# 2_AD9833.net
KiCad netlist of a schematic drawn in Altium Designer
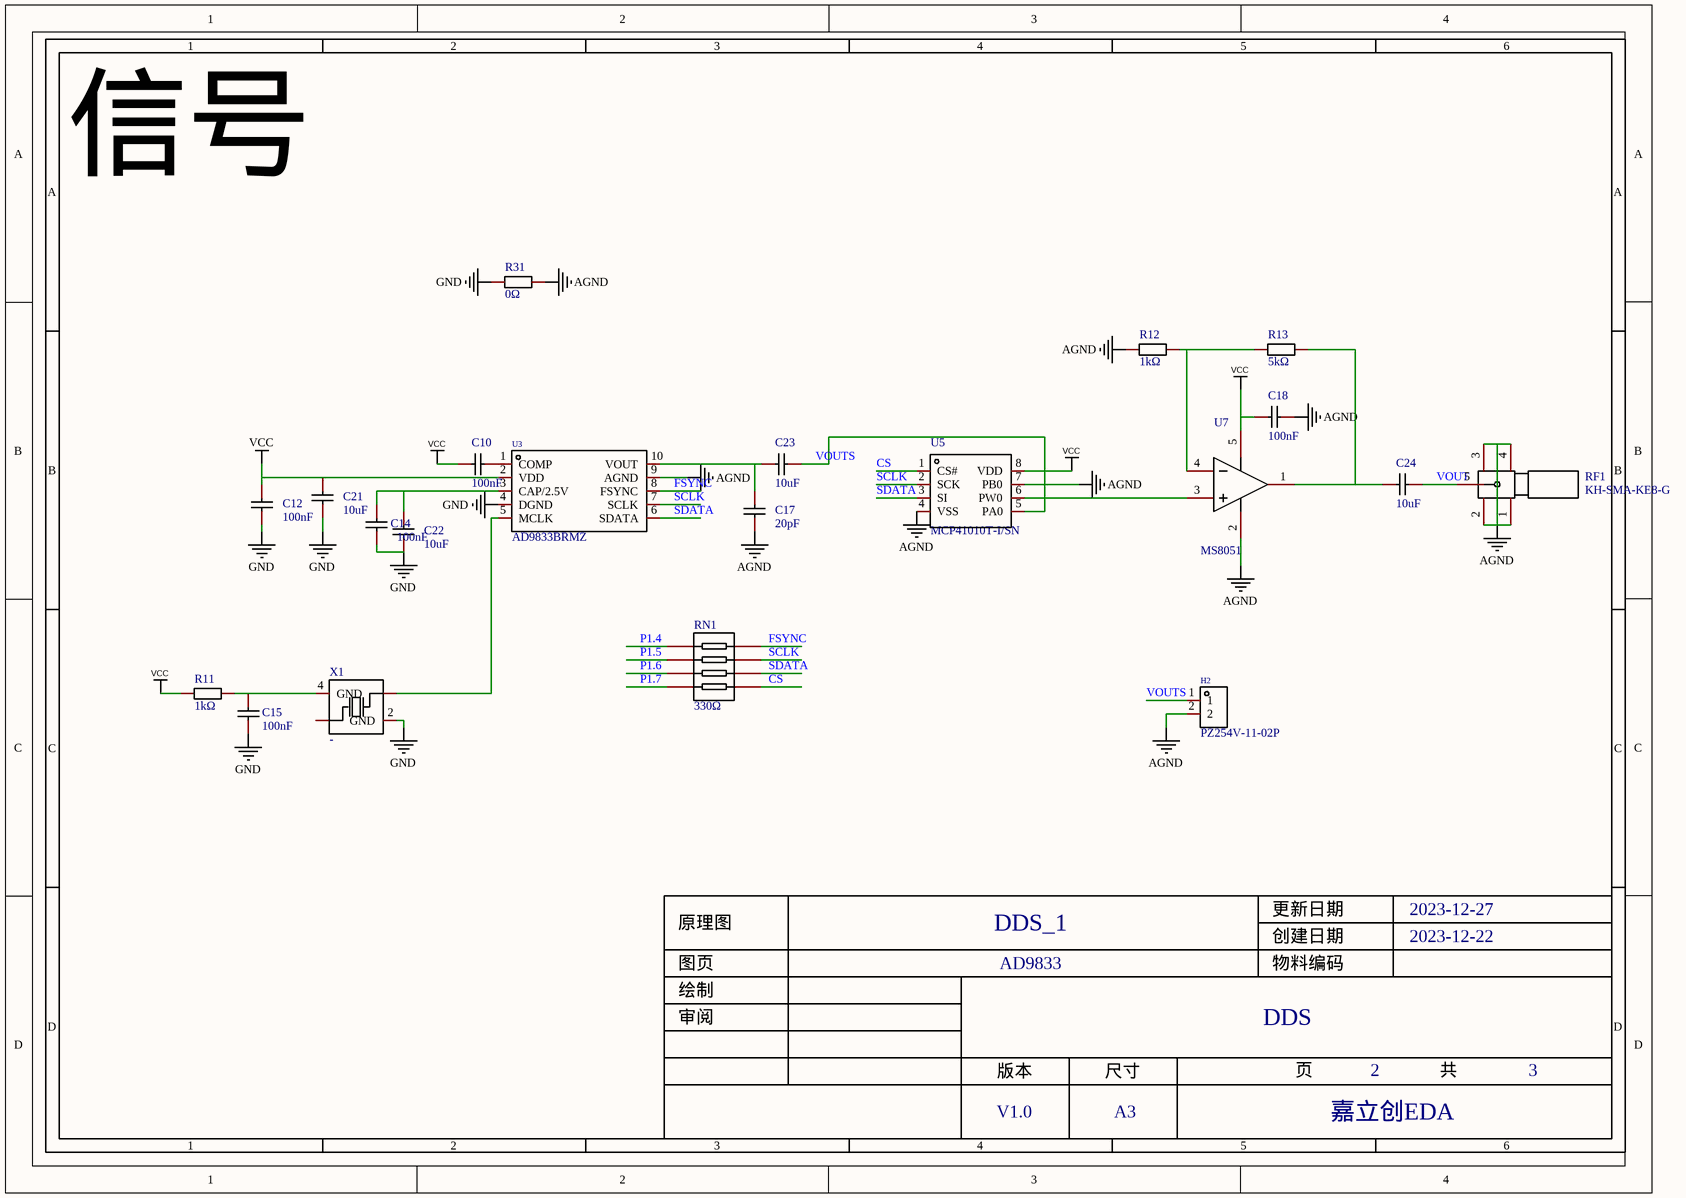
[diagram p0: 2_AD9833.schdoc]

(export (version "E")
  (design (tool "Eeschema 10.0.6"))
  (components
    (comp (ref "C10")
      (value "100nF")
      (description "容值:100nF;精度:±10%;额定电压:50V;材质(温度系数):X7R;")
      (fields
        (field (name "NAME") "100nF")
        (field (name "MANUFACTURER") "FH(风华)")
        (field (name "MANUFACTURER PART") "0805B104K500NT")
      )
      (libsource (lib "altium-import") (part "root_0_0805B104K500NT_"))
    )
    (comp (ref "C12")
      (value "100nF")
      (description "容值:100nF;精度:±10%;额定电压:50V;材质(温度系数):X7R;")
      (fields
        (field (name "NAME") "100nF")
        (field (name "MANUFACTURER") "FH(风华)")
        (field (name "MANUFACTURER PART") "0805B104K500NT")
      )
      (libsource (lib "altium-import") (part "root_1_0805B104K500NT_"))
    )
    (comp (ref "C14")
      (value "100nF")
      (description "容值:100nF;精度:±10%;额定电压:50V;材质(温度系数):X7R;")
      (fields
        (field (name "NAME") "100nF")
        (field (name "MANUFACTURER") "FH(风华)")
        (field (name "MANUFACTURER PART") "0805B104K500NT")
      )
      (libsource (lib "altium-import") (part "root_1_0805B104K500NT_"))
    )
    (comp (ref "C15")
      (value "100nF")
      (description "容值:100nF;精度:±10%;额定电压:50V;材质(温度系数):X7R;")
      (fields
        (field (name "NAME") "100nF")
        (field (name "MANUFACTURER") "FH(风华)")
        (field (name "MANUFACTURER PART") "0805B104K500NT")
      )
      (libsource (lib "altium-import") (part "root_1_0805B104K500NT_"))
    )
    (comp (ref "C17")
      (value "20pF")
      (description "容值:100nF;精度:±10%;额定电压:50V;材质(温度系数):X7R;")
      (fields
        (field (name "NAME") "20pF")
        (field (name "MANUFACTURER") "FH(风华)")
        (field (name "MANUFACTURER PART") "0805B104K500NT")
      )
      (libsource (lib "altium-import") (part "root_1_0805B104K500NT_"))
    )
    (comp (ref "C18")
      (value "100nF")
      (description "容值:100nF;精度:±10%;额定电压:50V;材质(温度系数):X7R;")
      (fields
        (field (name "NAME") "100nF")
        (field (name "MANUFACTURER") "FH(风华)")
        (field (name "MANUFACTURER PART") "0805B104K500NT")
      )
      (libsource (lib "altium-import") (part "root_0_0805B104K500NT_"))
    )
    (comp (ref "C21")
      (value "10uF")
      (description "容值:10uF;精度:±10%;额定电压:50V;材质(温度系数):X5R;")
      (fields
        (field (name "NAME") "10uF")
        (field (name "MANUFACTURER") "SAMSUNG(三星)")
        (field (name "MANUFACTURER PART") "CL31A106KBHNNNE")
      )
      (libsource (lib "altium-import") (part "root_1_CL31A106KBHNNNE_"))
    )
    (comp (ref "C22")
      (value "10uF")
      (description "容值:10uF;精度:±10%;额定电压:50V;材质(温度系数):X5R;")
      (fields
        (field (name "NAME") "10uF")
        (field (name "MANUFACTURER") "SAMSUNG(三星)")
        (field (name "MANUFACTURER PART") "CL31A106KBHNNNE")
      )
      (libsource (lib "altium-import") (part "root_1_CL31A106KBHNNNE_"))
    )
    (comp (ref "C23")
      (value "10uF")
      (description "容值:10uF;精度:±10%;额定电压:50V;材质(温度系数):X5R;")
      (fields
        (field (name "NAME") "10uF")
        (field (name "MANUFACTURER") "SAMSUNG(三星)")
        (field (name "MANUFACTURER PART") "CL31A106KBHNNNE")
      )
      (libsource (lib "altium-import") (part "root_0_CL31A106KBHNNNE_"))
    )
    (comp (ref "C24")
      (value "10uF")
      (description "容值:10uF;精度:±10%;额定电压:50V;材质(温度系数):X5R;")
      (fields
        (field (name "NAME") "10uF")
        (field (name "MANUFACTURER") "SAMSUNG(三星)")
        (field (name "MANUFACTURER PART") "CL31A106KBHNNNE")
      )
      (libsource (lib "altium-import") (part "root_0_CL31A106KBHNNNE_"))
    )
    (comp (ref "H2")
      (value "PZ254V-11-02P")
      (fields (field (name "NAME") "PZ254V-11-02P") (field (name "MANUFACTURER") "XFCN(兴飞)"))
      (libsource (lib "altium-import") (part "root_0_PZ254V-11-02P_"))
    )
    (comp (ref "R11")
      (value "1kΩ")
      (description "阻值:1kΩ;精度:±1%;功率:125mW;温度系数:±100ppm/℃;电阻类型:厚膜电阻;")
      (fields
        (field (name "NAME") "1kΩ")
        (field (name "MANUFACTURER") "UNI-ROYAL(厚声)")
        (field (name "MANUFACTURER PART") "0805W8F1001T5E")
      )
      (libsource (lib "altium-import") (part "root_0_0805W8F1001T5E_"))
    )
    (comp (ref "R12")
      (value "1kΩ")
      (description "阻值:1kΩ;精度:±1%;功率:125mW;温度系数:±100ppm/℃;电阻类型:厚膜电阻;")
      (fields
        (field (name "NAME") "1kΩ")
        (field (name "MANUFACTURER") "UNI-ROYAL(厚声)")
        (field (name "MANUFACTURER PART") "0805W8F1001T5E")
      )
      (libsource (lib "altium-import") (part "root_0_0805W8F1001T5E_"))
    )
    (comp (ref "R13")
      (value "5kΩ")
      (description "阻值:1kΩ;精度:±1%;功率:125mW;温度系数:±100ppm/℃;电阻类型:厚膜电阻;")
      (fields
        (field (name "NAME") "5kΩ")
        (field (name "MANUFACTURER") "UNI-ROYAL(厚声)")
        (field (name "MANUFACTURER PART") "0805W8F1001T5E")
      )
      (libsource (lib "altium-import") (part "root_0_0805W8F1001T5E_"))
    )
    (comp (ref "R31")
      (value "0Ω")
      (description "电阻类型:厚膜电阻;阻值:0Ω;精度:±1%;功率:125mW;")
      (fields
        (field (name "NAME") "0Ω")
        (field (name "MANUFACTURER") "UNI-ROYAL(厚声)")
        (field (name "MANUFACTURER PART") "0805W8F0000T5E")
      )
      (libsource (lib "altium-import") (part "root_0_0805W8F0000T5E_"))
    )
    (comp (ref "RF1")
      (value "KH-SMA-KE8-G")
      (description "连接器类型:板端;接口类型:内孔;频率-最大值:-;接口直径:-;射频系列:SMA;端口数量:1;阻抗:-;样式:偏脚;接口长度/高度:8mm;工作温度范围:-;")
      (fields (field (name "NAME") "KH-SMA-KE8-G") (field (name "MANUFACTURER") "kinghelm(金航标)"))
      (libsource (lib "altium-import") (part "root_2_KH-SMA-KE8-G_"))
    )
    (comp (ref "RN1")
      (value "330Ω")
      (description "阻值:330Ω;精度:±5%;单个元件功率:62.5mW;电阻器数:4;温度系数:±200ppm/℃;")
      (fields
        (field (name "NAME") "330Ω")
        (field (name "MANUFACTURER") "UNI-ROYAL(厚声)")
        (field (name "MANUFACTURER PART") "4D03WGJ0331T5E")
      )
      (libsource (lib "altium-import") (part "root_0_4D03WGJ0331T5E_"))
    )
    (comp (ref "U3")
      (value "AD9833BRMZ")
      (description "电源电压:2.3V~5.5V;分辨率(位):10;自宽调谐(最大值):28b;")
      (fields (field (name "NAME") "AD9833BRMZ") (field (name "MANUFACTURER") "ADI(亚德诺)"))
      (libsource (lib "altium-import") (part "root_0_AD9833BRMZ_"))
    )
    (comp (ref "U5")
      (value "MCP41010T-I/SN")
      (description "供电电压:2.7V~5.5V;电阻值(欧姆):10kΩ;精度:±20%;接口类型:SPI;")
      (fields (field (name "NAME") "MCP41010T-I/SN") (field (name "MANUFACTURER") "MICROCHIP(美国微芯)"))
      (libsource (lib "altium-import") (part "root_0_MCP41010T-I/SN_"))
    )
    (comp (ref "U7")
      (value "MS8051")
      (description "运放类型:-;放大器组数:-;增益带宽积（GBP）:-;压摆率（SR）:-;电源电压:-;各通道供电电流:-;")
      (fields (field (name "NAME") "MS8051") (field (name "MANUFACTURER") "Corebai(芯佰微)"))
      (libsource (lib "altium-import") (part "root_0_CBM8051AST5_"))
    )
    (comp (ref "X1")
      (value "-")
      (description "频率:-;负载电容:-;")
      (fields
        (field (name "NAME") "-")
        (field (name "MANUFACTURER") "TKD(泰晶)")
        (field (name "MANUFACTURER PART") "SX32Y025000BK1T")
      )
      (libsource (lib "altium-import") (part "root_0_SX32Y025000BK1T_"))
    )
  )
  (nets
    (net (code "1") (name "/CS") (class "Default")
      (node (ref "RN1") (pin "5") (pinfunction "5_5") (pintype "passive"))
      (node (ref "U5") (pin "1") (pinfunction "CS#_1") (pintype "passive"))
    )
    (net (code "2") (name "/FSYNC") (class "Default")
      (node (ref "RN1") (pin "8") (pinfunction "8_8") (pintype "passive"))
      (node (ref "U3") (pin "8") (pinfunction "FSYNC_8") (pintype "passive"))
    )
    (net (code "3") (name "/P1.4") (class "Default")
      (node (ref "RN1") (pin "1") (pinfunction "1_1") (pintype "passive"))
    )
    (net (code "4") (name "/P1.5") (class "Default")
      (node (ref "RN1") (pin "2") (pinfunction "2_2") (pintype "passive"))
    )
    (net (code "5") (name "/P1.6") (class "Default")
      (node (ref "RN1") (pin "3") (pinfunction "3_3") (pintype "passive"))
    )
    (net (code "6") (name "/P1.7") (class "Default")
      (node (ref "RN1") (pin "4") (pinfunction "4_4") (pintype "passive"))
    )
    (net (code "7") (name "/SCLK") (class "Default")
      (node (ref "RN1") (pin "7") (pinfunction "7_7") (pintype "passive"))
      (node (ref "U3") (pin "7") (pinfunction "SCLK_7") (pintype "passive"))
      (node (ref "U5") (pin "2") (pinfunction "SCK_2") (pintype "passive"))
    )
    (net (code "8") (name "/SDATA") (class "Default")
      (node (ref "RN1") (pin "6") (pinfunction "6_6") (pintype "passive"))
      (node (ref "U3") (pin "6") (pinfunction "SDATA_6") (pintype "passive"))
      (node (ref "U5") (pin "3") (pinfunction "SI_3") (pintype "passive"))
    )
    (net (code "9") (name "/VOUT") (class "Default")
      (node (ref "C24") (pin "2") (pinfunction "2_2") (pintype "passive"))
      (node (ref "RF1") (pin "5") (pinfunction "5_5") (pintype "passive"))
    )
    (net (code "10") (name "/VOUTS") (class "Default")
      (node (ref "C23") (pin "2") (pinfunction "2_2") (pintype "passive"))
      (node (ref "H2") (pin "1") (pinfunction "1_1") (pintype "passive"))
      (node (ref "U5") (pin "5") (pinfunction "PA0_5") (pintype "passive"))
    )
    (net (code "11") (name "AGND") (class "Default")
      (node (ref "C17") (pin "1") (pinfunction "1_1") (pintype "passive"))
      (node (ref "C18") (pin "2") (pinfunction "2_2") (pintype "passive"))
      (node (ref "H2") (pin "2") (pinfunction "2_2") (pintype "passive"))
      (node (ref "R12") (pin "1") (pinfunction "1_1") (pintype "passive"))
      (node (ref "R31") (pin "2") (pinfunction "2_2") (pintype "passive"))
      (node (ref "RF1") (pin "1") (pinfunction "1_1") (pintype "passive"))
      (node (ref "RF1") (pin "2") (pinfunction "2_2") (pintype "passive"))
      (node (ref "RF1") (pin "3") (pinfunction "3_3") (pintype "passive"))
      (node (ref "RF1") (pin "4") (pinfunction "4_4") (pintype "passive"))
      (node (ref "U3") (pin "9") (pinfunction "AGND_9") (pintype "passive"))
      (node (ref "U5") (pin "4") (pinfunction "VSS_4") (pintype "passive"))
      (node (ref "U5") (pin "7") (pinfunction "PB0_7") (pintype "passive"))
      (node (ref "U7") (pin "2") (pinfunction "VSS_2") (pintype "passive"))
    )
    (net (code "12") (name "GND") (class "Default")
      (node (ref "C12") (pin "1") (pinfunction "1_1") (pintype "passive"))
      (node (ref "C14") (pin "1") (pinfunction "1_1") (pintype "passive"))
      (node (ref "C15") (pin "1") (pinfunction "1_1") (pintype "passive"))
      (node (ref "C21") (pin "1") (pinfunction "1_1") (pintype "passive"))
      (node (ref "C22") (pin "1") (pinfunction "1_1") (pintype "passive"))
      (node (ref "R31") (pin "1") (pinfunction "1_1") (pintype "passive"))
      (node (ref "U3") (pin "4") (pinfunction "DGND_4") (pintype "passive"))
      (node (ref "X1") (pin "2") (pinfunction "GND_2") (pintype "passive"))
    )
    (net (code "13") (name "Net-(C15-Pad2)") (class "Default")
      (node (ref "C15") (pin "2") (pinfunction "2_2") (pintype "passive"))
      (node (ref "R11") (pin "2") (pinfunction "2_2") (pintype "passive"))
      (node (ref "X1") (pin "4") (pinfunction "GND_4") (pintype "passive"))
    )
    (net (code "14") (name "Net-(U3-CAP{slash}2.5V)") (class "Default")
      (node (ref "C14") (pin "2") (pinfunction "2_2") (pintype "passive"))
      (node (ref "C22") (pin "2") (pinfunction "2_2") (pintype "passive"))
      (node (ref "U3") (pin "3") (pinfunction "CAP/2.5V_3") (pintype "passive"))
    )
    (net (code "15") (name "Net-(U3-COMP)") (class "Default")
      (node (ref "C10") (pin "2") (pinfunction "2_2") (pintype "passive"))
      (node (ref "U3") (pin "1") (pinfunction "COMP_1") (pintype "passive"))
    )
    (net (code "16") (name "Net-(U3-MCLK)") (class "Default")
      (node (ref "U3") (pin "5") (pinfunction "MCLK_5") (pintype "passive"))
      (node (ref "X1") (pin "3") (pinfunction "OSC2_3") (pintype "passive"))
    )
    (net (code "17") (name "Net-(U3-VOUT)") (class "Default")
      (node (ref "C17") (pin "2") (pinfunction "2_2") (pintype "passive"))
      (node (ref "C23") (pin "1") (pinfunction "1_1") (pintype "passive"))
      (node (ref "U3") (pin "10") (pinfunction "VOUT_10") (pintype "passive"))
    )
    (net (code "18") (name "Net-(U5-PW0)") (class "Default")
      (node (ref "U5") (pin "6") (pinfunction "PW0_6") (pintype "passive"))
      (node (ref "U7") (pin "3") (pinfunction "IN+_3") (pintype "passive"))
    )
    (net (code "19") (name "Net-(U7-IN-)") (class "Default")
      (node (ref "R12") (pin "2") (pinfunction "2_2") (pintype "passive"))
      (node (ref "R13") (pin "1") (pinfunction "1_1") (pintype "passive"))
      (node (ref "U7") (pin "4") (pinfunction "IN-_4") (pintype "passive"))
    )
    (net (code "20") (name "Net-(U7-OUT)") (class "Default")
      (node (ref "C24") (pin "1") (pinfunction "1_1") (pintype "passive"))
      (node (ref "R13") (pin "2") (pinfunction "2_2") (pintype "passive"))
      (node (ref "U7") (pin "1") (pinfunction "OUT_1") (pintype "passive"))
    )
    (net (code "21") (name "VCC") (class "Default")
      (node (ref "C10") (pin "1") (pinfunction "1_1") (pintype "passive"))
      (node (ref "C12") (pin "2") (pinfunction "2_2") (pintype "passive"))
      (node (ref "C18") (pin "1") (pinfunction "1_1") (pintype "passive"))
      (node (ref "C21") (pin "2") (pinfunction "2_2") (pintype "passive"))
      (node (ref "R11") (pin "1") (pinfunction "1_1") (pintype "passive"))
      (node (ref "U3") (pin "2") (pinfunction "VDD_2") (pintype "passive"))
      (node (ref "U5") (pin "8") (pinfunction "VDD_8") (pintype "passive"))
      (node (ref "U7") (pin "5") (pinfunction "VDD_5") (pintype "passive"))
    )
    (net (code "22") (name "unconnected-(X1-OSC1-Pad1)") (class "Default")
      (node (ref "X1") (pin "1") (pinfunction "OSC1_1") (pintype "passive"))
    )
  )
)
